# LZ3003_1.net
KiCad netlist of a schematic drawn in EAGLE
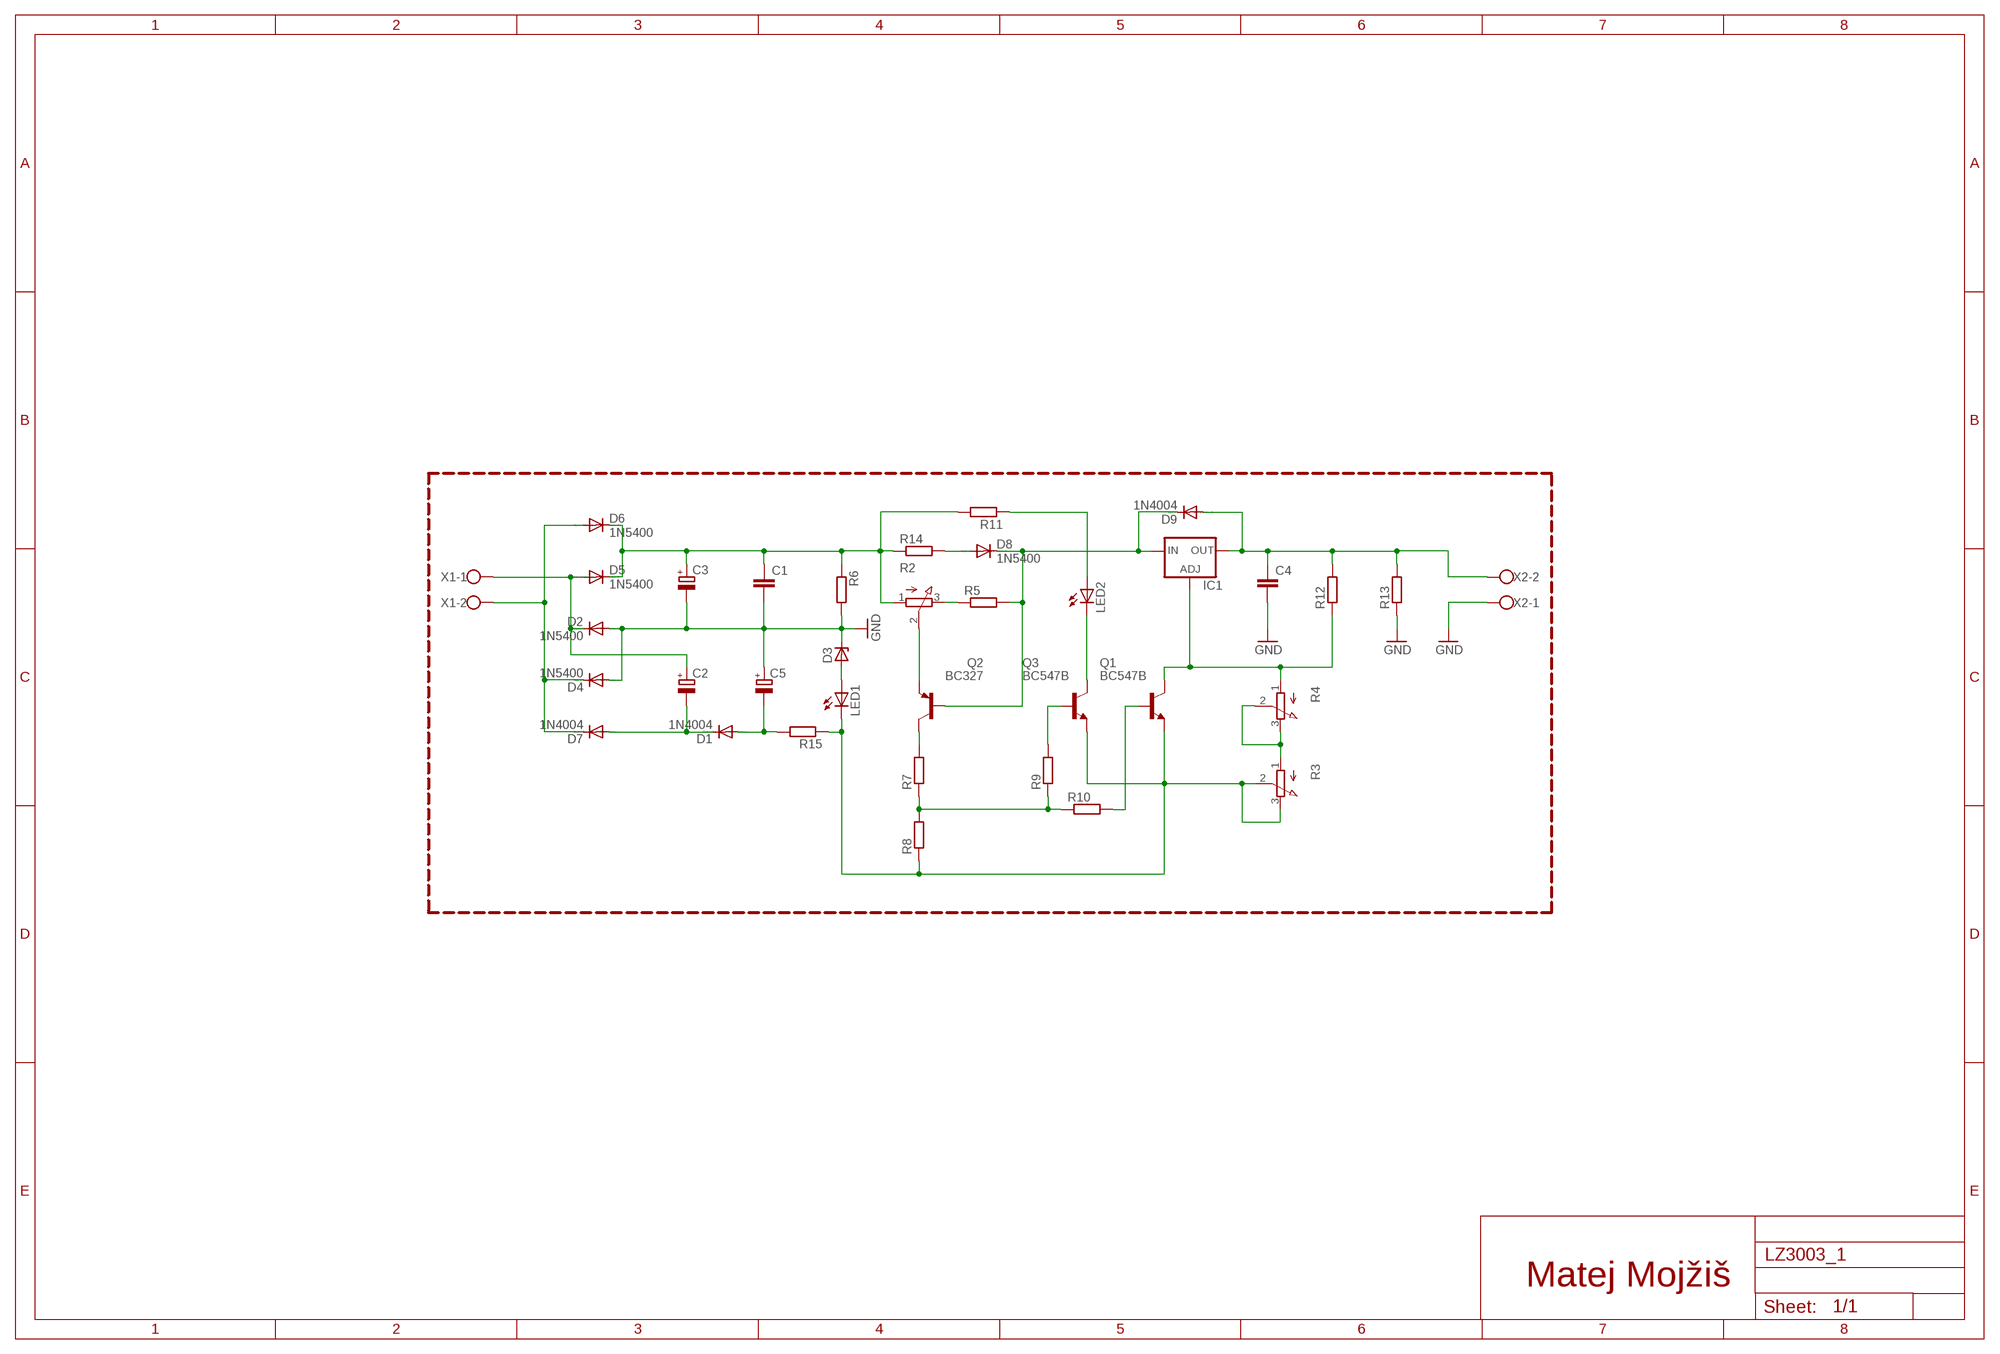
[diagram p0: schematic, sheet 1]

(export (version "E")
  (design (tool "Eeschema 10.0.6"))
  (components
    (comp (ref "C1")
      (value "C-EU050-025X075")
      (footprint "eagle-import:C050-025X075")
      (libsource (lib "eagle-import") (part "C-EU050-025X075"))
    )
    (comp (ref "C2")
      (value "CPOL-EUE5-8.5")
      (footprint "eagle-import:E5-8,5")
      (libsource (lib "eagle-import") (part "CPOL-EUE5-8.5"))
    )
    (comp (ref "C3")
      (value "CPOL-EUE7.5-16")
      (footprint "eagle-import:E7,5-16")
      (libsource (lib "eagle-import") (part "CPOL-EUE7.5-16"))
    )
    (comp (ref "C4")
      (value "C-EU050-025X075")
      (footprint "eagle-import:C050-025X075")
      (libsource (lib "eagle-import") (part "C-EU050-025X075"))
    )
    (comp (ref "C5")
      (value "CPOL-EUE5-8.5")
      (footprint "eagle-import:E5-8,5")
      (libsource (lib "eagle-import") (part "CPOL-EUE5-8.5"))
    )
    (comp (ref "D1")
      (value "1N4004")
      (footprint "eagle-import:DO41-10")
      (libsource (lib "eagle-import") (part "1N4004"))
    )
    (comp (ref "D2")
      (value "1N5400")
      (footprint "eagle-import:DO201-15")
      (libsource (lib "eagle-import") (part "1N5400"))
    )
    (comp (ref "D3")
      (value "ZENER-DIODEDO34-7")
      (footprint "eagle-import:DO34Z7")
      (libsource (lib "eagle-import") (part "ZENER-DIODEDO34-7"))
    )
    (comp (ref "D4")
      (value "1N5400")
      (footprint "eagle-import:DO201-15")
      (libsource (lib "eagle-import") (part "1N5400"))
    )
    (comp (ref "D5")
      (value "1N5400")
      (footprint "eagle-import:DO201-15")
      (libsource (lib "eagle-import") (part "1N5400"))
    )
    (comp (ref "D6")
      (value "1N5400")
      (footprint "eagle-import:DO201-15")
      (libsource (lib "eagle-import") (part "1N5400"))
    )
    (comp (ref "D7")
      (value "1N4004")
      (footprint "eagle-import:DO41-10")
      (libsource (lib "eagle-import") (part "1N4004"))
    )
    (comp (ref "D8")
      (value "1N5400")
      (footprint "eagle-import:DO201-15")
      (libsource (lib "eagle-import") (part "1N5400"))
    )
    (comp (ref "D9")
      (value "1N4004")
      (footprint "eagle-import:DO41-10")
      (libsource (lib "eagle-import") (part "1N4004"))
    )
    (comp (ref "IC1")
      (value "LM317TS")
      (footprint "eagle-import:317TS")
      (libsource (lib "eagle-import") (part "LM317TS"))
    )
    (comp (ref "LED1")
      (value "LED5MM")
      (footprint "eagle-import:LED5MM")
      (libsource (lib "eagle-import") (part "LED5MM"))
    )
    (comp (ref "LED2")
      (value "LED5MM")
      (footprint "eagle-import:LED5MM")
      (libsource (lib "eagle-import") (part "LED5MM"))
    )
    (comp (ref "Q1")
      (value "BC547B")
      (footprint "eagle-import:TO92")
      (libsource (lib "eagle-import") (part "BC547B"))
    )
    (comp (ref "Q2")
      (value "BC327")
      (footprint "eagle-import:TO92-EBC")
      (libsource (lib "eagle-import") (part "BC327"))
    )
    (comp (ref "Q3")
      (value "BC547B")
      (footprint "eagle-import:TO92")
      (libsource (lib "eagle-import") (part "BC547B"))
    )
    (comp (ref "R2")
      (value "3RP/1610N")
      (footprint "eagle-import:3RP_1610N")
      (libsource (lib "eagle-import") (part "3RP/1610N"))
    )
    (comp (ref "R3")
      (value "3RP/1610N")
      (footprint "eagle-import:3RP_1610N")
      (libsource (lib "eagle-import") (part "3RP/1610N"))
    )
    (comp (ref "R4")
      (value "3RP/1610N")
      (footprint "eagle-import:3RP_1610N")
      (libsource (lib "eagle-import") (part "3RP/1610N"))
    )
    (comp (ref "R5")
      (value "R-EU_0207/7")
      (footprint "eagle-import:0207_7")
      (libsource (lib "eagle-import") (part "R-EU_0207/7"))
    )
    (comp (ref "R6")
      (value "R-EU_0207/7")
      (footprint "eagle-import:0207_7")
      (libsource (lib "eagle-import") (part "R-EU_0207/7"))
    )
    (comp (ref "R7")
      (value "R-EU_0207/7")
      (footprint "eagle-import:0207_7")
      (libsource (lib "eagle-import") (part "R-EU_0207/7"))
    )
    (comp (ref "R8")
      (value "R-EU_0207/7")
      (footprint "eagle-import:0207_7")
      (libsource (lib "eagle-import") (part "R-EU_0207/7"))
    )
    (comp (ref "R9")
      (value "R-EU_0207/7")
      (footprint "eagle-import:0207_7")
      (libsource (lib "eagle-import") (part "R-EU_0207/7"))
    )
    (comp (ref "R10")
      (value "R-EU_0207/7")
      (footprint "eagle-import:0207_7")
      (libsource (lib "eagle-import") (part "R-EU_0207/7"))
    )
    (comp (ref "R11")
      (value "R-EU_0207/7")
      (footprint "eagle-import:0207_7")
      (libsource (lib "eagle-import") (part "R-EU_0207/7"))
    )
    (comp (ref "R12")
      (value "R-EU_0207/7")
      (footprint "eagle-import:0207_7")
      (libsource (lib "eagle-import") (part "R-EU_0207/7"))
    )
    (comp (ref "R13")
      (value "R-EU_0207/7")
      (footprint "eagle-import:0207_7")
      (libsource (lib "eagle-import") (part "R-EU_0207/7"))
    )
    (comp (ref "R14")
      (value "R-EU_VTA52")
      (footprint "eagle-import:VTA52")
      (libsource (lib "eagle-import") (part "R-EU_VTA52"))
    )
    (comp (ref "R15")
      (value "R-EU_0207/7")
      (footprint "eagle-import:0207_7")
      (libsource (lib "eagle-import") (part "R-EU_0207/7"))
    )
    (comp (ref "X1")
      (value "W237-102")
      (footprint "eagle-import:W237-102")
      (fields (field (name "MPN") "237-102"))
      (libsource (lib "eagle-import") (part "W237-102"))
    )
    (comp (ref "X2")
      (value "W237-102")
      (footprint "eagle-import:W237-102")
      (fields (field (name "MPN") "237-102"))
      (libsource (lib "eagle-import") (part "W237-102"))
    )
  )
  (nets
    (net (code "1") (name "GND") (class "Default")
      (node (ref "C1") (pin "2") (pinfunction "2_2") (pintype "passive"))
      (node (ref "C3") (pin "-") (pinfunction "-_-") (pintype "passive"))
      (node (ref "C4") (pin "2") (pinfunction "2_2") (pintype "passive"))
      (node (ref "C5") (pin "+") (pinfunction "+_+") (pintype "passive"))
      (node (ref "D2") (pin "A") (pinfunction "A_A") (pintype "passive"))
      (node (ref "D3") (pin "C") (pinfunction "C_C") (pintype "passive"))
      (node (ref "D4") (pin "A") (pinfunction "A_A") (pintype "passive"))
      (node (ref "R13") (pin "1") (pinfunction "1_1") (pintype "passive"))
      (node (ref "R6") (pin "2") (pinfunction "2_2") (pintype "passive"))
      (node (ref "X2") (pin "1") (pinfunction "KL_1") (pintype "passive"))
    )
    (net (code "2") (name "Net-(C2-Pad-)") (class "Default")
      (node (ref "C2") (pin "-") (pinfunction "-_-") (pintype "passive"))
      (node (ref "D1") (pin "C") (pinfunction "C_C") (pintype "passive"))
      (node (ref "D7") (pin "A") (pinfunction "A_A") (pintype "passive"))
    )
    (net (code "3") (name "Net-(C5-Pad-)") (class "Default")
      (node (ref "C5") (pin "-") (pinfunction "-_-") (pintype "passive"))
      (node (ref "D1") (pin "A") (pinfunction "A_A") (pintype "passive"))
      (node (ref "R15") (pin "2") (pinfunction "2_2") (pintype "passive"))
    )
    (net (code "4") (name "Net-(D3-PadA)") (class "Default")
      (node (ref "D3") (pin "A") (pinfunction "A_A") (pintype "passive"))
      (node (ref "LED1") (pin "A") (pinfunction "A_A") (pintype "passive"))
    )
    (net (code "5") (name "Net-(D8-PadA)") (class "Default")
      (node (ref "D8") (pin "A") (pinfunction "A_A") (pintype "passive"))
      (node (ref "R14") (pin "2") (pinfunction "2_2") (pintype "passive"))
    )
    (net (code "6") (name "Net-(IC1-ADJ)") (class "Default")
      (node (ref "IC1") (pin "1") (pinfunction "ADJ_1") (pintype "input"))
      (node (ref "Q1") (pin "3") (pinfunction "C_3") (pintype "passive"))
      (node (ref "R12") (pin "1") (pinfunction "1_1") (pintype "passive"))
      (node (ref "R4") (pin "1") (pinfunction "A_1") (pintype "passive"))
    )
    (net (code "7") (name "Net-(IC1-IN)") (class "Default")
      (node (ref "D8") (pin "C") (pinfunction "C_C") (pintype "passive"))
      (node (ref "D9") (pin "C") (pinfunction "C_C") (pintype "passive"))
      (node (ref "IC1") (pin "3") (pinfunction "IN_3") (pintype "input"))
      (node (ref "Q2") (pin "B") (pinfunction "B_B") (pintype "passive"))
      (node (ref "R5") (pin "2") (pinfunction "2_2") (pintype "passive"))
    )
    (net (code "8") (name "Net-(IC1-OUT)") (class "Default")
      (node (ref "C4") (pin "1") (pinfunction "1_1") (pintype "passive"))
      (node (ref "D9") (pin "A") (pinfunction "A_A") (pintype "passive"))
      (node (ref "IC1") (pin "2") (pinfunction "OUT_2") (pintype "passive"))
      (node (ref "R12") (pin "2") (pinfunction "2_2") (pintype "passive"))
      (node (ref "R13") (pin "2") (pinfunction "2_2") (pintype "passive"))
      (node (ref "X2") (pin "2") (pinfunction "KL_2") (pintype "passive"))
    )
    (net (code "9") (name "Net-(LED1-C)") (class "Default")
      (node (ref "LED1") (pin "K") (pinfunction "C_K") (pintype "passive"))
      (node (ref "Q1") (pin "1") (pinfunction "E_1") (pintype "passive"))
      (node (ref "Q3") (pin "1") (pinfunction "E_1") (pintype "passive"))
      (node (ref "R15") (pin "1") (pinfunction "1_1") (pintype "passive"))
      (node (ref "R3") (pin "2") (pinfunction "S_2") (pintype "passive"))
      (node (ref "R3") (pin "3") (pinfunction "E_3") (pintype "passive"))
      (node (ref "R8") (pin "1") (pinfunction "1_1") (pintype "passive"))
    )
    (net (code "10") (name "Net-(LED2-C)") (class "Default")
      (node (ref "LED2") (pin "K") (pinfunction "C_K") (pintype "passive"))
      (node (ref "Q3") (pin "3") (pinfunction "C_3") (pintype "passive"))
    )
    (net (code "11") (name "Net-(LED2-PadA)") (class "Default")
      (node (ref "LED2") (pin "A") (pinfunction "A_A") (pintype "passive"))
      (node (ref "R11") (pin "1") (pinfunction "1_1") (pintype "passive"))
    )
    (net (code "12") (name "Net-(Q1-B)") (class "Default")
      (node (ref "Q1") (pin "2") (pinfunction "B_2") (pintype "passive"))
      (node (ref "R10") (pin "2") (pinfunction "2_2") (pintype "passive"))
    )
    (net (code "13") (name "Net-(Q2-PadC)") (class "Default")
      (node (ref "Q2") (pin "C") (pinfunction "C_C") (pintype "passive"))
      (node (ref "R7") (pin "2") (pinfunction "2_2") (pintype "passive"))
    )
    (net (code "14") (name "Net-(Q3-B)") (class "Default")
      (node (ref "Q3") (pin "2") (pinfunction "B_2") (pintype "passive"))
      (node (ref "R9") (pin "2") (pinfunction "2_2") (pintype "passive"))
    )
    (net (code "15") (name "Net-(R2-A)") (class "Default")
      (node (ref "C1") (pin "1") (pinfunction "1_1") (pintype "passive"))
      (node (ref "C3") (pin "+") (pinfunction "+_+") (pintype "passive"))
      (node (ref "D5") (pin "C") (pinfunction "C_C") (pintype "passive"))
      (node (ref "D6") (pin "C") (pinfunction "C_C") (pintype "passive"))
      (node (ref "R11") (pin "2") (pinfunction "2_2") (pintype "passive"))
      (node (ref "R14") (pin "1") (pinfunction "1_1") (pintype "passive"))
      (node (ref "R2") (pin "1") (pinfunction "A_1") (pintype "passive"))
      (node (ref "R6") (pin "1") (pinfunction "1_1") (pintype "passive"))
    )
    (net (code "16") (name "Net-(R2-E)") (class "Default")
      (node (ref "R2") (pin "3") (pinfunction "E_3") (pintype "passive"))
      (node (ref "R5") (pin "1") (pinfunction "1_1") (pintype "passive"))
    )
    (net (code "17") (name "Net-(R2-S)") (class "Default")
      (node (ref "Q2") (pin "E") (pinfunction "E_E") (pintype "passive"))
      (node (ref "R2") (pin "2") (pinfunction "S_2") (pintype "passive"))
    )
    (net (code "18") (name "Net-(R3-A)") (class "Default")
      (node (ref "R3") (pin "1") (pinfunction "A_1") (pintype "passive"))
      (node (ref "R4") (pin "2") (pinfunction "S_2") (pintype "passive"))
      (node (ref "R4") (pin "3") (pinfunction "E_3") (pintype "passive"))
    )
    (net (code "19") (name "Net-(R10-Pad1)") (class "Default")
      (node (ref "R10") (pin "1") (pinfunction "1_1") (pintype "passive"))
      (node (ref "R7") (pin "1") (pinfunction "1_1") (pintype "passive"))
      (node (ref "R8") (pin "2") (pinfunction "2_2") (pintype "passive"))
      (node (ref "R9") (pin "1") (pinfunction "1_1") (pintype "passive"))
    )
    (net (code "20") (name "Net-(X1A-KL)") (class "Default")
      (node (ref "C2") (pin "+") (pinfunction "+_+") (pintype "passive"))
      (node (ref "D2") (pin "C") (pinfunction "C_C") (pintype "passive"))
      (node (ref "D5") (pin "A") (pinfunction "A_A") (pintype "passive"))
      (node (ref "X1") (pin "1") (pinfunction "KL_1") (pintype "passive"))
    )
    (net (code "21") (name "Net-(X1B-KL)") (class "Default")
      (node (ref "D4") (pin "C") (pinfunction "C_C") (pintype "passive"))
      (node (ref "D6") (pin "A") (pinfunction "A_A") (pintype "passive"))
      (node (ref "D7") (pin "C") (pinfunction "C_C") (pintype "passive"))
      (node (ref "X1") (pin "2") (pinfunction "KL_2") (pintype "passive"))
    )
  )
)
